# SensorFimPapel.net
KiCad netlist of a schematic drawn in Altium Designer
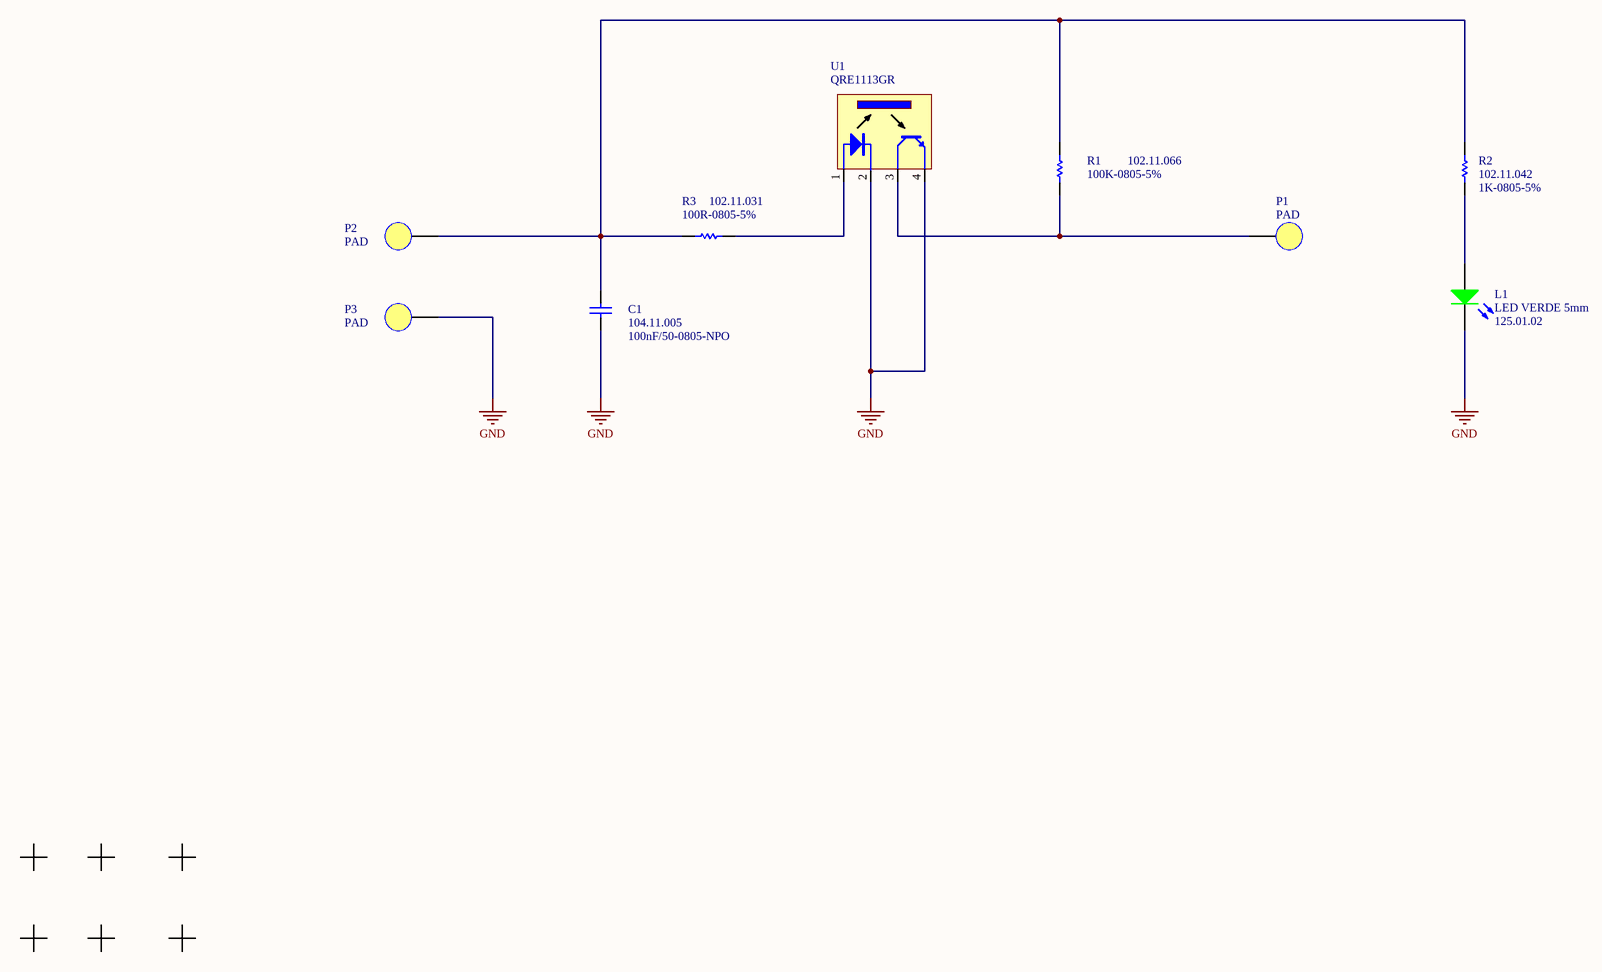
[diagram p0: SensorFimPapel.SchDoc]

(export (version "E")
  (design (tool "Eeschema 10.0.6"))
  (components
    (comp (ref "C1")
      (value "100nF/50-0805-NPO")
      (footprint "0805-REVISADO ONDA")
      (fields (field (name "ERP") "104.11.005"))
      (libsource (lib "AquinoLib") (part "100nF/50-0805-NPO"))
    )
    (comp (ref "FD1")
      (value "FID")
      (footprint "FIDUCIAL")
      (libsource (lib "ChaveDigital3") (part "FIDUCIAL"))
    )
    (comp (ref "FD2")
      (value "FID")
      (footprint "FIDUCIAL")
      (libsource (lib "ChaveDigital3") (part "FIDUCIAL"))
    )
    (comp (ref "FD3")
      (value "FID")
      (footprint "FIDUCIAL")
      (libsource (lib "ChaveDigital3") (part "FIDUCIAL"))
    )
    (comp (ref "FD4")
      (value "FID")
      (footprint "FIDUCIAL")
      (libsource (lib "ChaveDigital3") (part "FIDUCIAL"))
    )
    (comp (ref "FD5")
      (value "FID")
      (footprint "FIDUCIAL")
      (libsource (lib "ChaveDigital3") (part "FIDUCIAL"))
    )
    (comp (ref "FD6")
      (value "FID")
      (footprint "FIDUCIAL")
      (libsource (lib "ChaveDigital3") (part "FIDUCIAL"))
    )
    (comp (ref "L1")
      (value "LED VERDE 5mm")
      (footprint "LED 0805 - REVISADO ONDA")
      (fields (field (name "ERP") "125.01.02"))
      (libsource (lib "AquinoLib") (part "LED VERDE 5mm"))
    )
    (comp (ref "P1") (value "PAD") (footprint "PAD 3,5") (libsource (lib "ChaveDigital3") (part "PAD")))
    (comp (ref "P2") (value "PAD") (footprint "PAD 3,5") (libsource (lib "ChaveDigital3") (part "PAD")))
    (comp (ref "P3") (value "PAD") (footprint "PAD 3,5") (libsource (lib "ChaveDigital3") (part "PAD")))
    (comp (ref "R1")
      (value "100K-0805-5%")
      (footprint "0805-REVISADO ONDA")
      (fields (field (name "ERP") "102.11.066"))
      (libsource (lib "AquinoLib") (part "100K-0805-5%"))
    )
    (comp (ref "R2")
      (value "1K-0805-5%")
      (footprint "0805-REVISADO ONDA")
      (fields (field (name "ERP") "102.11.042"))
      (libsource (lib "AquinoLib") (part "1K-0805-5%"))
    )
    (comp (ref "R3")
      (value "100R-0805-5%")
      (footprint "0805-REVISADO ONDA")
      (fields (field (name "ERP") "102.11.031"))
      (libsource (lib "AquinoLib") (part "100R-0805-5%"))
    )
    (comp (ref "U1")
      (value "QRE1113GR")
      (footprint "QR1113")
      (libsource (lib "AquinoLib") (part "QRE1113GR"))
    )
  )
  (nets
    (net (code "1") (name "GND") (class "Default")
      (node (ref "C1") (pin "1") (pinfunction "1_1") (pintype "passive"))
      (node (ref "L1") (pin "2") (pinfunction "K_2") (pintype "passive"))
      (node (ref "P3") (pin "1") (pinfunction "1_1") (pintype "passive"))
      (node (ref "U1") (pin "2") (pinfunction "K_2") (pintype "passive"))
      (node (ref "U1") (pin "4") (pinfunction "4_4") (pintype "passive"))
    )
    (net (code "2") (name "Net-(C1-Pad2)") (class "Default")
      (node (ref "C1") (pin "2") (pinfunction "2_2") (pintype "passive"))
      (node (ref "P2") (pin "1") (pinfunction "1_1") (pintype "passive"))
      (node (ref "R1") (pin "2") (pinfunction "2_2") (pintype "passive"))
      (node (ref "R2") (pin "2") (pinfunction "2_2") (pintype "passive"))
      (node (ref "R3") (pin "1") (pinfunction "1_1") (pintype "passive"))
    )
    (net (code "3") (name "Net-(L1-A)") (class "Default")
      (node (ref "L1") (pin "1") (pinfunction "A_1") (pintype "passive"))
      (node (ref "R2") (pin "1") (pinfunction "1_1") (pintype "passive"))
    )
    (net (code "4") (name "Net-(P1-Pad1)") (class "Default")
      (node (ref "P1") (pin "1") (pinfunction "1_1") (pintype "passive"))
      (node (ref "R1") (pin "1") (pinfunction "1_1") (pintype "passive"))
      (node (ref "U1") (pin "3") (pinfunction "3_3") (pintype "passive"))
    )
    (net (code "5") (name "Net-(U1-A)") (class "Default")
      (node (ref "R3") (pin "2") (pinfunction "2_2") (pintype "passive"))
      (node (ref "U1") (pin "1") (pinfunction "A_1") (pintype "passive"))
    )
  )
)
